# Sheet_1_2020-07-29_17-40-03.net
KiCad netlist of a schematic drawn in Altium Designer
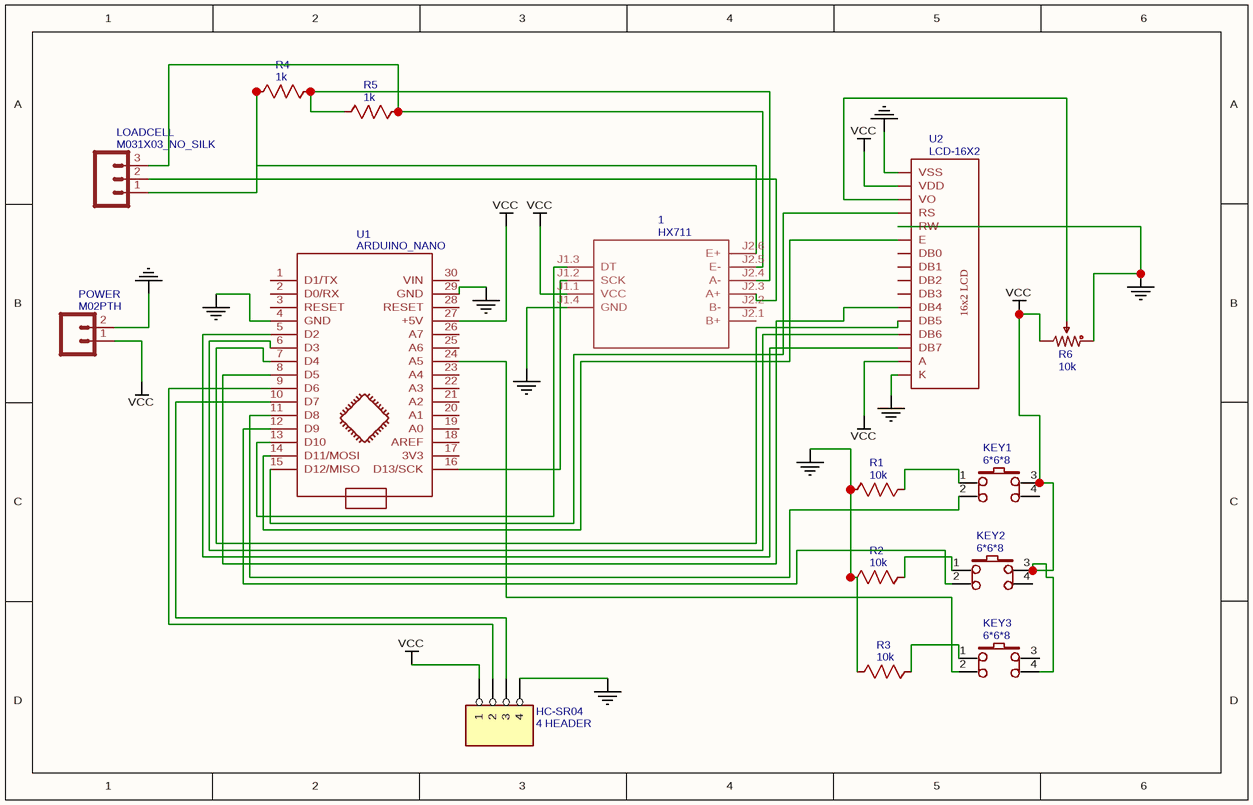
[diagram p0: Sheet_1_2020-07-29_17-40-03.schdoc]

(export (version "E")
  (design (tool "Eeschema 10.0.6"))
  (components
    (comp (ref "1")
      (value "HX711")
      (fields (field (name "BOM_MANUFACTURER PART") "?") (field (name "CONTRIBUTOR") "Krzysztof Handzlik"))
      (libsource (lib "altium-import") (part "root_0_HX711_"))
    )
    (comp (ref "HC-SR04")
      (value "4 HEADER")
      (description "4 Pin Header")
      (fields (field (name "BOM_MANUFACTURER PART") "?"))
      (libsource (lib "altium-import") (part "root_1_4 HEADER_"))
    )
    (comp (ref "KEY1")
      (value "6*6*8")
      (fields
        (field (name "BOM_SUPPLIER PART") "C59982")
        (field (name "BOM_MANUFACTURER PART") "button6*6*8")
      )
      (libsource (lib "altium-import") (part "root_0_6*6*8_"))
    )
    (comp (ref "KEY2")
      (value "6*6*8")
      (fields
        (field (name "BOM_SUPPLIER PART") "C59982")
        (field (name "BOM_MANUFACTURER PART") "button6*6*8")
      )
      (libsource (lib "altium-import") (part "root_0_6*6*8_"))
    )
    (comp (ref "KEY3")
      (value "6*6*8")
      (fields
        (field (name "BOM_SUPPLIER PART") "C59982")
        (field (name "BOM_MANUFACTURER PART") "button6*6*8")
      )
      (libsource (lib "altium-import") (part "root_0_6*6*8_"))
    )
    (comp (ref "LOADCELL")
      (value "M031X03_NO_SILK")
      (description "Header 3")
      (fields (field (name "BOM_MANUFACTURER PART") "?"))
      (libsource (lib "altium-import") (part "root_0_M031X03_NO_SILK_"))
    )
    (comp (ref "POWER")
      (value "M02PTH")
      (description "Header 2")
      (fields (field (name "BOM_MANUFACTURER PART") "?"))
      (libsource (lib "altium-import") (part "root_0_M02PTH_"))
    )
    (comp (ref "R1")
      (value "10k")
      (fields (field (name "BOM_MANUFACTURER PART") "?"))
      (libsource (lib "altium-import") (part "root_0_10k_"))
    )
    (comp (ref "R2")
      (value "10k")
      (fields (field (name "BOM_MANUFACTURER PART") "?"))
      (libsource (lib "altium-import") (part "root_0_10k_"))
    )
    (comp (ref "R3")
      (value "10k")
      (fields (field (name "BOM_MANUFACTURER PART") "?"))
      (libsource (lib "altium-import") (part "root_0_10k_"))
    )
    (comp (ref "R4")
      (value "1k")
      (fields (field (name "BOM_MANUFACTURER PART") "?"))
      (libsource (lib "altium-import") (part "root_0_1k_"))
    )
    (comp (ref "R5")
      (value "1k")
      (fields (field (name "BOM_MANUFACTURER PART") "?"))
      (libsource (lib "altium-import") (part "root_0_1k_"))
    )
    (comp (ref "R6")
      (value "10k")
      (fields
        (field (name "BOM_MANUFACTURER PART") "3386P-1-101LF")
        (field (name "BOM_SUPPLIER PART") "C125022")
        (field (name "CONTRIBUTOR") "EasyEDA")
      )
      (libsource (lib "") (part "root_0_10k__1"))
    )
    (comp (ref "U1")
      (value "ARDUINO_NANO")
      (fields (field (name "BOM_MANUFACTURER PART") "?"))
      (libsource (lib "altium-import") (part "root_0_ARDUINO_NANO_"))
    )
    (comp (ref "U2")
      (value "LCD-16X2")
      (fields (field (name "BOM_MANUFACTURER PART") "?") (field (name "CONTRIBUTOR") "SparkFun"))
      (libsource (lib "altium-import") (part "root_0_LCD-16X2_"))
    )
  )
  (nets
    (net (code "1") (name "GND") (class "Default")
      (node (ref "1") (pin "J1.4") (pinfunction "GND_J1.4") (pintype "passive"))
      (node (ref "HC-SR04") (pin "4") (pinfunction "4_4") (pintype "passive"))
      (node (ref "POWER") (pin "2") (pinfunction "2_2") (pintype "passive"))
      (node (ref "R1") (pin "1") (pinfunction "1_1") (pintype "passive"))
      (node (ref "R2") (pin "1") (pinfunction "1_1") (pintype "passive"))
      (node (ref "R3") (pin "1") (pinfunction "1_1") (pintype "passive"))
      (node (ref "R6") (pin "1") (pinfunction "1_1") (pintype "passive"))
      (node (ref "U1") (pin "29") (pinfunction "GND_29") (pintype "passive"))
      (node (ref "U1") (pin "4") (pinfunction "GND_4") (pintype "passive"))
      (node (ref "U2") (pin "1") (pinfunction "VSS_1") (pintype "passive"))
      (node (ref "U2") (pin "16") (pinfunction "K_16") (pintype "passive"))
      (node (ref "U2") (pin "5") (pinfunction "RW_5") (pintype "passive"))
    )
    (net (code "2") (name "Net-(1-A+)") (class "Default")
      (node (ref "1") (pin "J2.3") (pinfunction "A+_J2.3") (pintype "passive"))
      (node (ref "LOADCELL") (pin "2") (pinfunction "2_2") (pintype "passive"))
    )
    (net (code "3") (name "Net-(1-A-)") (class "Default")
      (node (ref "1") (pin "J2.4") (pinfunction "A-_J2.4") (pintype "passive"))
      (node (ref "R4") (pin "2") (pinfunction "2_2") (pintype "passive"))
      (node (ref "R5") (pin "1") (pinfunction "1_1") (pintype "passive"))
    )
    (net (code "4") (name "Net-(1-DT)") (class "Default")
      (node (ref "1") (pin "J1.3") (pinfunction "DT_J1.3") (pintype "passive"))
      (node (ref "U1") (pin "13") (pinfunction "D10_13") (pintype "passive"))
    )
    (net (code "5") (name "Net-(1-E+)") (class "Default")
      (node (ref "1") (pin "J2.6") (pinfunction "E+_J2.6") (pintype "passive"))
      (node (ref "LOADCELL") (pin "1") (pinfunction "1_1") (pintype "passive"))
      (node (ref "R4") (pin "1") (pinfunction "1_1") (pintype "passive"))
    )
    (net (code "6") (name "Net-(1-E-)") (class "Default")
      (node (ref "1") (pin "J2.5") (pinfunction "E-_J2.5") (pintype "passive"))
      (node (ref "LOADCELL") (pin "3") (pinfunction "3_3") (pintype "passive"))
      (node (ref "R5") (pin "2") (pinfunction "2_2") (pintype "passive"))
    )
    (net (code "7") (name "Net-(1-SCK)") (class "Default")
      (node (ref "1") (pin "J1.2") (pinfunction "SCK_J1.2") (pintype "passive"))
      (node (ref "U1") (pin "16") (pinfunction "D13/SCK_16") (pintype "passive"))
    )
    (net (code "8") (name "Net-(KEY1-Pad1)") (class "Default")
      (node (ref "KEY1") (pin "1") (pinfunction "1_1") (pintype "passive"))
      (node (ref "R1") (pin "2") (pinfunction "2_2") (pintype "passive"))
    )
    (net (code "9") (name "Net-(KEY2-Pad1)") (class "Default")
      (node (ref "KEY2") (pin "1") (pinfunction "1_1") (pintype "passive"))
      (node (ref "R2") (pin "2") (pinfunction "2_2") (pintype "passive"))
    )
    (net (code "10") (name "Net-(KEY3-Pad1)") (class "Default")
      (node (ref "KEY3") (pin "1") (pinfunction "1_1") (pintype "passive"))
      (node (ref "R3") (pin "2") (pinfunction "2_2") (pintype "passive"))
    )
    (net (code "11") (name "Net-(U1-A5)") (class "Default")
      (node (ref "KEY3") (pin "2") (pinfunction "2_2") (pintype "passive"))
      (node (ref "U1") (pin "24") (pinfunction "A5_24") (pintype "passive"))
    )
    (net (code "12") (name "Net-(U1-D2)") (class "Default")
      (node (ref "U1") (pin "5") (pinfunction "D2_5") (pintype "passive"))
      (node (ref "U2") (pin "14") (pinfunction "DB7_14") (pintype "passive"))
    )
    (net (code "13") (name "Net-(U1-D3)") (class "Default")
      (node (ref "U1") (pin "6") (pinfunction "D3_6") (pintype "passive"))
      (node (ref "U2") (pin "13") (pinfunction "DB6_13") (pintype "passive"))
    )
    (net (code "14") (name "Net-(U1-D4)") (class "Default")
      (node (ref "U1") (pin "7") (pinfunction "D4_7") (pintype "passive"))
      (node (ref "U2") (pin "12") (pinfunction "DB5_12") (pintype "passive"))
    )
    (net (code "15") (name "Net-(U1-D5)") (class "Default")
      (node (ref "U1") (pin "8") (pinfunction "D5_8") (pintype "passive"))
      (node (ref "U2") (pin "11") (pinfunction "DB4_11") (pintype "passive"))
    )
    (net (code "16") (name "Net-(U1-D6)") (class "Default")
      (node (ref "HC-SR04") (pin "2") (pinfunction "2_2") (pintype "passive"))
      (node (ref "U1") (pin "9") (pinfunction "D6_9") (pintype "passive"))
    )
    (net (code "17") (name "Net-(U1-D7)") (class "Default")
      (node (ref "HC-SR04") (pin "3") (pinfunction "3_3") (pintype "passive"))
      (node (ref "U1") (pin "10") (pinfunction "D7_10") (pintype "passive"))
    )
    (net (code "18") (name "Net-(U1-D8)") (class "Default")
      (node (ref "KEY1") (pin "2") (pinfunction "2_2") (pintype "passive"))
      (node (ref "U1") (pin "11") (pinfunction "D8_11") (pintype "passive"))
    )
    (net (code "19") (name "Net-(U1-D9)") (class "Default")
      (node (ref "KEY2") (pin "2") (pinfunction "2_2") (pintype "passive"))
      (node (ref "U1") (pin "12") (pinfunction "D9_12") (pintype "passive"))
    )
    (net (code "20") (name "Net-(U1-D11{slash}MOSI)") (class "Default")
      (node (ref "U1") (pin "14") (pinfunction "D11/MOSI_14") (pintype "passive"))
      (node (ref "U2") (pin "6") (pinfunction "E_6") (pintype "passive"))
    )
    (net (code "21") (name "Net-(U1-D12{slash}MISO)") (class "Default")
      (node (ref "U1") (pin "15") (pinfunction "D12/MISO_15") (pintype "passive"))
      (node (ref "U2") (pin "4") (pinfunction "RS_4") (pintype "passive"))
    )
    (net (code "22") (name "Net-(U2-VO)") (class "Default")
      (node (ref "R6") (pin "2") (pinfunction "2_2") (pintype "passive"))
      (node (ref "U2") (pin "3") (pinfunction "VO_3") (pintype "passive"))
    )
    (net (code "23") (name "VCC") (class "Default")
      (node (ref "1") (pin "J1.1") (pinfunction "VCC_J1.1") (pintype "passive"))
      (node (ref "HC-SR04") (pin "1") (pinfunction "1_1") (pintype "passive"))
      (node (ref "KEY1") (pin "3") (pinfunction "3_3") (pintype "passive"))
      (node (ref "KEY2") (pin "3") (pinfunction "3_3") (pintype "passive"))
      (node (ref "KEY3") (pin "4") (pinfunction "4_4") (pintype "passive"))
      (node (ref "POWER") (pin "1") (pinfunction "1_1") (pintype "passive"))
      (node (ref "R6") (pin "3") (pinfunction "3_3") (pintype "passive"))
      (node (ref "U1") (pin "27") (pinfunction "+5V_27") (pintype "passive"))
      (node (ref "U2") (pin "15") (pinfunction "A_15") (pintype "passive"))
      (node (ref "U2") (pin "2") (pinfunction "VDD_2") (pintype "passive"))
    )
    (net (code "24") (name "unconnected-(1-B+-PadJ2.1)") (class "Default")
      (node (ref "1") (pin "J2.1") (pinfunction "B+_J2.1") (pintype "passive"))
    )
    (net (code "25") (name "unconnected-(1-B--PadJ2.2)") (class "Default")
      (node (ref "1") (pin "J2.2") (pinfunction "B-_J2.2") (pintype "passive"))
    )
    (net (code "26") (name "unconnected-(KEY1-Pad4)") (class "Default")
      (node (ref "KEY1") (pin "4") (pinfunction "4_4") (pintype "passive"))
    )
    (net (code "27") (name "unconnected-(KEY2-Pad4)") (class "Default")
      (node (ref "KEY2") (pin "4") (pinfunction "4_4") (pintype "passive"))
    )
    (net (code "28") (name "unconnected-(KEY3-Pad3)") (class "Default")
      (node (ref "KEY3") (pin "3") (pinfunction "3_3") (pintype "passive"))
    )
    (net (code "29") (name "unconnected-(U1-3V3-Pad17)") (class "Default")
      (node (ref "U1") (pin "17") (pinfunction "3V3_17") (pintype "passive"))
    )
    (net (code "30") (name "unconnected-(U1-A0-Pad19)") (class "Default")
      (node (ref "U1") (pin "19") (pinfunction "A0_19") (pintype "passive"))
    )
    (net (code "31") (name "unconnected-(U1-A1-Pad20)") (class "Default")
      (node (ref "U1") (pin "20") (pinfunction "A1_20") (pintype "passive"))
    )
    (net (code "32") (name "unconnected-(U1-A2-Pad21)") (class "Default")
      (node (ref "U1") (pin "21") (pinfunction "A2_21") (pintype "passive"))
    )
    (net (code "33") (name "unconnected-(U1-A3-Pad22)") (class "Default")
      (node (ref "U1") (pin "22") (pinfunction "A3_22") (pintype "passive"))
    )
    (net (code "34") (name "unconnected-(U1-A4-Pad23)") (class "Default")
      (node (ref "U1") (pin "23") (pinfunction "A4_23") (pintype "passive"))
    )
    (net (code "35") (name "unconnected-(U1-A6-Pad25)") (class "Default")
      (node (ref "U1") (pin "25") (pinfunction "A6_25") (pintype "passive"))
    )
    (net (code "36") (name "unconnected-(U1-A7-Pad26)") (class "Default")
      (node (ref "U1") (pin "26") (pinfunction "A7_26") (pintype "passive"))
    )
    (net (code "37") (name "unconnected-(U1-AREF-Pad18)") (class "Default")
      (node (ref "U1") (pin "18") (pinfunction "AREF_18") (pintype "passive"))
    )
    (net (code "38") (name "unconnected-(U1-D0{slash}RX-Pad2)") (class "Default")
      (node (ref "U1") (pin "2") (pinfunction "D0/RX_2") (pintype "passive"))
    )
    (net (code "39") (name "unconnected-(U1-D1{slash}TX-Pad1)") (class "Default")
      (node (ref "U1") (pin "1") (pinfunction "D1/TX_1") (pintype "passive"))
    )
    (net (code "40") (name "unconnected-(U1-RESET-Pad3)") (class "Default")
      (node (ref "U1") (pin "3") (pinfunction "RESET_3") (pintype "passive"))
    )
    (net (code "41") (name "unconnected-(U1-RESET-Pad28)") (class "Default")
      (node (ref "U1") (pin "28") (pinfunction "RESET_28") (pintype "passive"))
    )
    (net (code "42") (name "unconnected-(U1-VIN-Pad30)") (class "Default")
      (node (ref "U1") (pin "30") (pinfunction "VIN_30") (pintype "passive"))
    )
    (net (code "43") (name "unconnected-(U2-DB0-Pad7)") (class "Default")
      (node (ref "U2") (pin "7") (pinfunction "DB0_7") (pintype "passive"))
    )
    (net (code "44") (name "unconnected-(U2-DB1-Pad8)") (class "Default")
      (node (ref "U2") (pin "8") (pinfunction "DB1_8") (pintype "passive"))
    )
    (net (code "45") (name "unconnected-(U2-DB2-Pad9)") (class "Default")
      (node (ref "U2") (pin "9") (pinfunction "DB2_9") (pintype "passive"))
    )
    (net (code "46") (name "unconnected-(U2-DB3-Pad10)") (class "Default")
      (node (ref "U2") (pin "10") (pinfunction "DB3_10") (pintype "passive"))
    )
  )
)
